# MAX-M8Q_GPS_FeatherWing.net
KiCad netlist of a schematic drawn in EAGLE
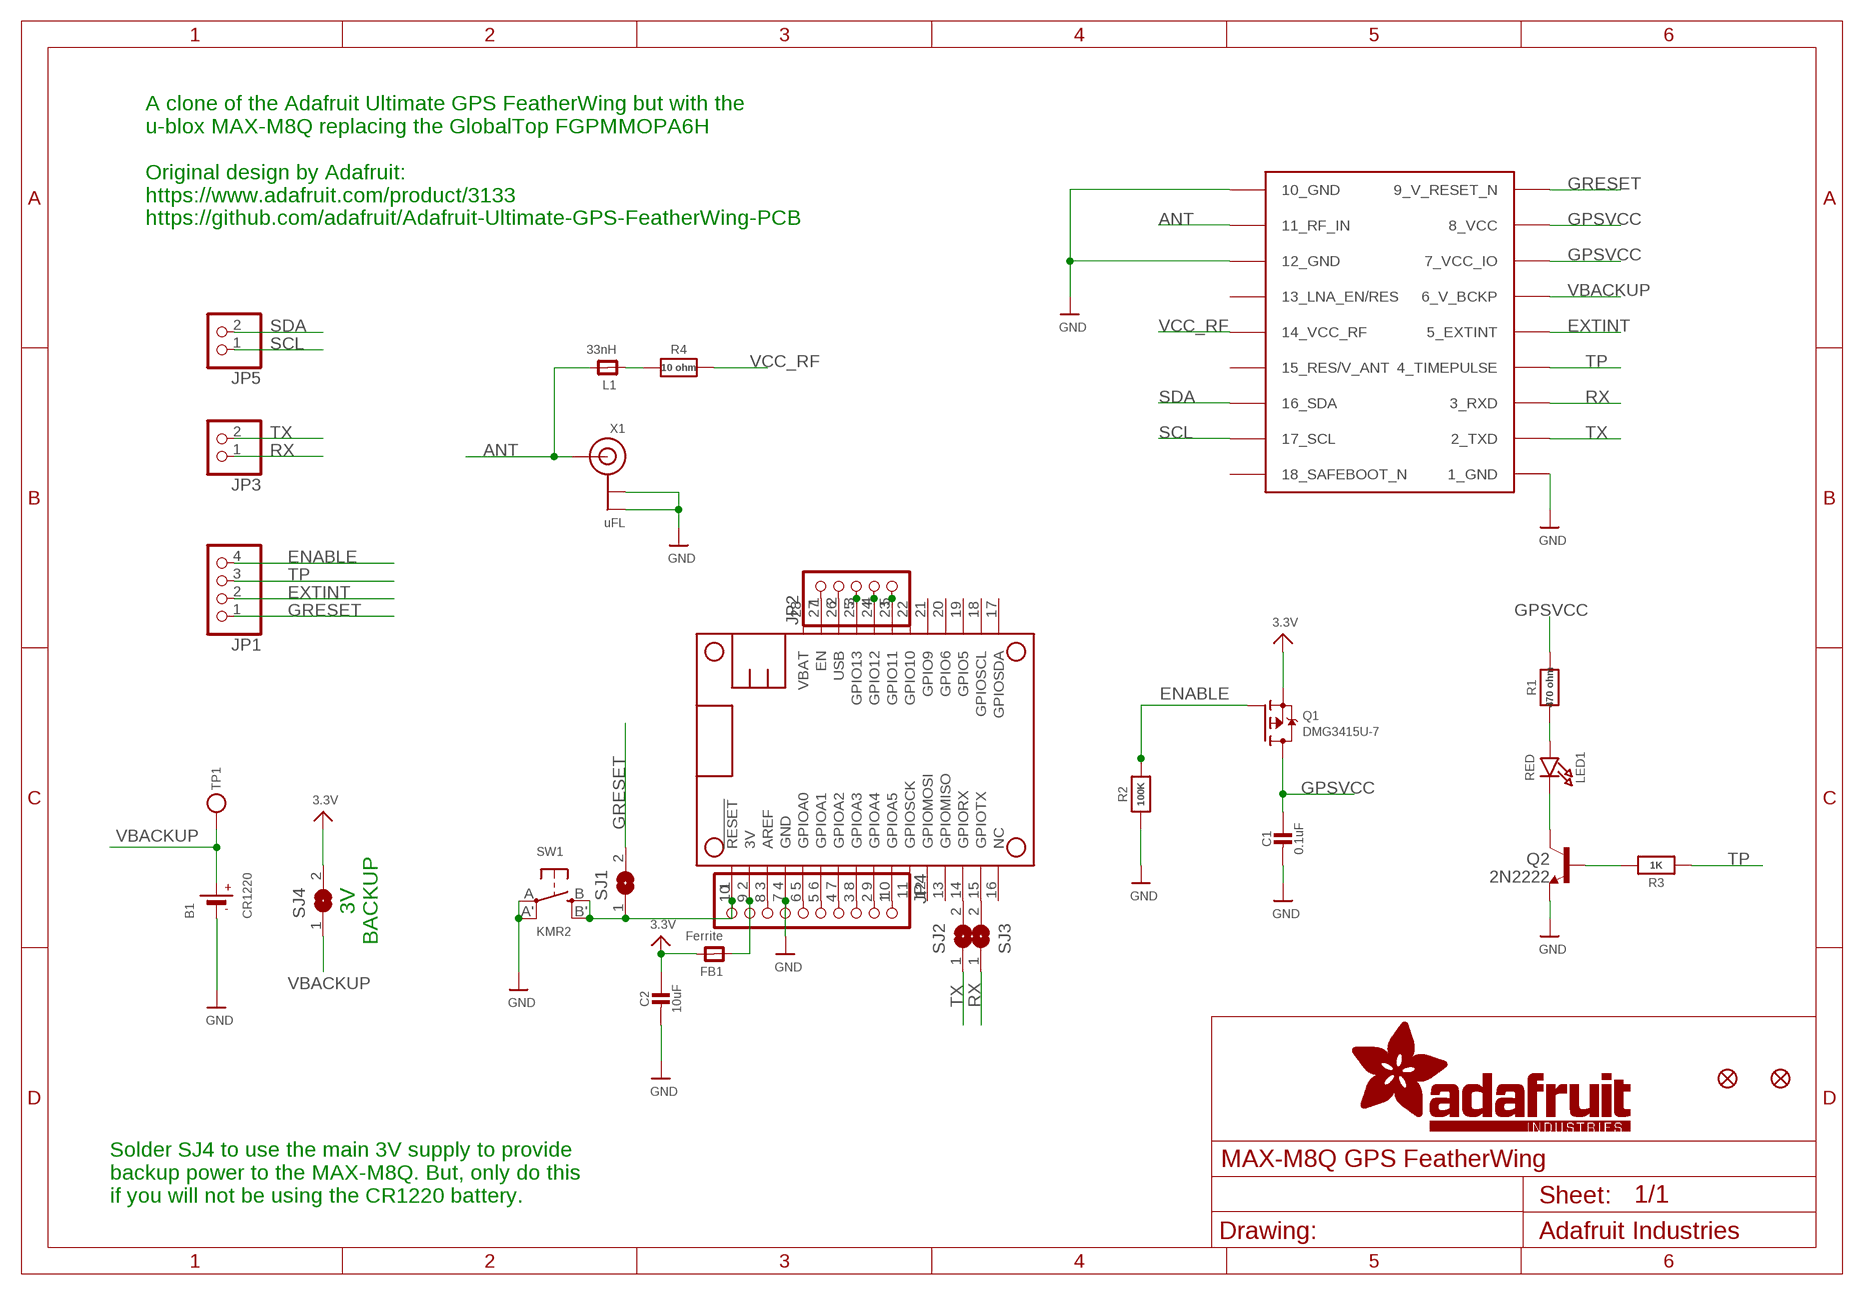
[diagram p0: schematic, sheet 1]

(export (version "E")
  (design (tool "Eeschema 10.0.6"))
  (components
    (comp (ref "B1")
      (value "CR1220")
      (footprint "eagle-import:CR1220-2")
      (libsource (lib "eagle-import") (part "BATTERYCR1220_2"))
    )
    (comp (ref "C1")
      (value "0.1uF")
      (footprint "eagle-import:0805-NO")
      (libsource (lib "eagle-import") (part "CAP_CERAMIC0805-NOOUTLINE"))
    )
    (comp (ref "C2")
      (value "10uF")
      (footprint "eagle-import:0805-NO")
      (libsource (lib "eagle-import") (part "CAP_CERAMIC0805-NOOUTLINE"))
    )
    (comp (ref "FB1")
      (value "Ferrite")
      (footprint "eagle-import:0805-NO")
      (libsource (lib "eagle-import") (part "FERRITE-0805NO"))
    )
    (comp (ref "FID1")
      (value "FIDUCIAL\"\"")
      (footprint "eagle-import:FIDUCIAL_1MM")
      (libsource (lib "eagle-import") (part "FIDUCIAL{dblquote}{dblquote}"))
    )
    (comp (ref "FID2")
      (value "FIDUCIAL\"\"")
      (footprint "eagle-import:FIDUCIAL_1MM")
      (libsource (lib "eagle-import") (part "FIDUCIAL{dblquote}{dblquote}"))
    )
    (comp (ref "JP1")
      (value "HEADER-1X4ROUND")
      (footprint "eagle-import:1X04_ROUND")
      (libsource (lib "eagle-import") (part "HEADER-1X4ROUND"))
    )
    (comp (ref "JP2")
      (value "HEADER-1X570MIL")
      (footprint "eagle-import:1X05_ROUND_70")
      (libsource (lib "eagle-import") (part "HEADER-1X570MIL"))
    )
    (comp (ref "JP3")
      (value "HEADER-1X2ROUND")
      (footprint "eagle-import:1X02_ROUND")
      (libsource (lib "eagle-import") (part "HEADER-1X2ROUND"))
    )
    (comp (ref "JP4")
      (value "HEADER-1X10ROUND")
      (footprint "eagle-import:1X10_ROUND")
      (libsource (lib "eagle-import") (part "HEADER-1X10ROUND"))
    )
    (comp (ref "JP5")
      (value "HEADER-1X2ROUND")
      (footprint "eagle-import:1X02_ROUND")
      (libsource (lib "eagle-import") (part "HEADER-1X2ROUND"))
    )
    (comp (ref "L1")
      (value "33nH")
      (footprint "eagle-import:0805-NO")
      (libsource (lib "eagle-import") (part "FERRITE-0805NO"))
    )
    (comp (ref "LED1")
      (value "RED")
      (footprint "eagle-import:CHIPLED_0805_NOOUTLINE")
      (libsource (lib "eagle-import") (part "LED0805_NOOUTLINE"))
    )
    (comp (ref "MS1")
      (value "FEATHERWING")
      (footprint "eagle-import:FEATHERWING")
      (libsource (lib "eagle-import") (part "FEATHERWING"))
    )
    (comp (ref "Q1")
      (value "DMG3415U-7")
      (footprint "eagle-import:SOT23-WIDE")
      (libsource (lib "eagle-import") (part "MOSFET-PWIDE"))
    )
    (comp (ref "Q2")
      (value "2N2222")
      (footprint "eagle-import:SOT23-BEC")
      (libsource (lib "eagle-import") (part "-NPN-SOT23-BECMMBT2222ALT1"))
    )
    (comp (ref "R1")
      (value "470 ohm")
      (footprint "eagle-import:0805-NO")
      (libsource (lib "eagle-import") (part "RESISTOR0805_NOOUTLINE"))
    )
    (comp (ref "R2")
      (value "100K")
      (footprint "eagle-import:0805-NO")
      (libsource (lib "eagle-import") (part "RESISTOR0805_NOOUTLINE"))
    )
    (comp (ref "R3")
      (value "1K")
      (footprint "eagle-import:0805-NO")
      (libsource (lib "eagle-import") (part "RESISTOR0805_NOOUTLINE"))
    )
    (comp (ref "R4")
      (value "10 ohm")
      (footprint "eagle-import:0805-NO")
      (libsource (lib "eagle-import") (part "RESISTOR0805_NOOUTLINE"))
    )
    (comp (ref "SJ1")
      (value "SOLDERJUMPER")
      (footprint "eagle-import:SOLDERJUMPER_ARROW_NOPASTE")
      (libsource (lib "eagle-import") (part "SOLDERJUMPER"))
    )
    (comp (ref "SJ2")
      (value "SOLDERJUMPERCLOSED")
      (footprint "eagle-import:SOLDERJUMPER_CLOSEDWIRE")
      (libsource (lib "eagle-import") (part "SOLDERJUMPERCLOSED"))
    )
    (comp (ref "SJ3")
      (value "SOLDERJUMPERCLOSED")
      (footprint "eagle-import:SOLDERJUMPER_CLOSEDWIRE")
      (libsource (lib "eagle-import") (part "SOLDERJUMPERCLOSED"))
    )
    (comp (ref "SJ4") (value "SJ") (footprint "eagle-import:SJ") (libsource (lib "eagle-import") (part "SJ")))
    (comp (ref "SW1")
      (value "KMR2")
      (footprint "eagle-import:BTN_KMR2_4.6X2.8")
      (libsource (lib "eagle-import") (part "SWITCH_TACT_SMT4.6X2.8"))
    )
    (comp (ref "TP1")
      (value "TESTPOINTROUND1.5MM")
      (footprint "eagle-import:TESTPOINT_ROUND_1.5MM")
      (libsource (lib "eagle-import") (part "TESTPOINTROUND1.5MM"))
    )
    (comp (ref "U1")
      (value "MAX-M8")
      (footprint "eagle-import:MAX-M8")
      (libsource (lib "eagle-import") (part "MAX-M8"))
    )
    (comp (ref "X1")
      (value "uFL")
      (footprint "eagle-import:U.FL")
      (libsource (lib "eagle-import") (part "ANTENNA_U.FL"))
    )
  )
  (nets
    (net (code "1") (name "/ANT") (class "Default")
      (node (ref "L1") (pin "2") (pinfunction "P$2_2") (pintype "passive"))
      (node (ref "U1") (pin "11_RF_IN") (pinfunction "11_RF_IN_11_RF_IN") (pintype "bidirectional"))
      (node (ref "X1") (pin "3") (pinfunction "SIGNAL_3") (pintype "passive"))
    )
    (net (code "2") (name "/ENABLE") (class "Default")
      (node (ref "JP1") (pin "4") (pinfunction "4_4") (pintype "passive"))
      (node (ref "Q1") (pin "1") (pinfunction "G_1") (pintype "passive"))
      (node (ref "R2") (pin "2") (pinfunction "2_2") (pintype "passive"))
    )
    (net (code "3") (name "/EXTINT") (class "Default")
      (node (ref "JP1") (pin "2") (pinfunction "2_2") (pintype "passive"))
      (node (ref "U1") (pin "5_EXTINT") (pinfunction "5_EXTINT_5_EXTINT") (pintype "bidirectional"))
    )
    (net (code "4") (name "/GPSVCC") (class "Default")
      (node (ref "C1") (pin "1") (pinfunction "1_1") (pintype "passive"))
      (node (ref "Q1") (pin "3") (pinfunction "D_3") (pintype "passive"))
      (node (ref "R1") (pin "2") (pinfunction "2_2") (pintype "passive"))
      (node (ref "U1") (pin "7_VCC_IO") (pinfunction "7_VCC_IO_7_VCC_IO") (pintype "power_in"))
      (node (ref "U1") (pin "8_VCC") (pinfunction "8_VCC_8_VCC") (pintype "power_in"))
    )
    (net (code "5") (name "/GRESET") (class "Default")
      (node (ref "JP1") (pin "1") (pinfunction "1_1") (pintype "passive"))
      (node (ref "SJ1") (pin "2") (pinfunction "2_2") (pintype "passive"))
      (node (ref "U1") (pin "9_RESET_N") (pinfunction "9_V_RESET_N_9_RESET_N") (pintype "power_in"))
    )
    (net (code "6") (name "/RX") (class "Default")
      (node (ref "JP3") (pin "1") (pinfunction "1_1") (pintype "passive"))
      (node (ref "SJ3") (pin "1") (pinfunction "1_1") (pintype "passive"))
      (node (ref "U1") (pin "3_RXD") (pinfunction "3_RXD_3_RXD") (pintype "bidirectional"))
    )
    (net (code "7") (name "/SCL") (class "Default")
      (node (ref "JP5") (pin "1") (pinfunction "1_1") (pintype "passive"))
      (node (ref "U1") (pin "17_SCL") (pinfunction "17_SCL_17_SCL") (pintype "bidirectional"))
    )
    (net (code "8") (name "/SDA") (class "Default")
      (node (ref "JP5") (pin "2") (pinfunction "2_2") (pintype "passive"))
      (node (ref "U1") (pin "16_SDA") (pinfunction "16_SDA_16_SDA") (pintype "bidirectional"))
    )
    (net (code "9") (name "/TP") (class "Default")
      (node (ref "JP1") (pin "3") (pinfunction "3_3") (pintype "passive"))
      (node (ref "R3") (pin "1") (pinfunction "1_1") (pintype "passive"))
      (node (ref "U1") (pin "4_TIMEPULSE") (pinfunction "4_TIMEPULSE_4_TIMEPULSE") (pintype "bidirectional"))
    )
    (net (code "10") (name "/TX") (class "Default")
      (node (ref "JP3") (pin "2") (pinfunction "2_2") (pintype "passive"))
      (node (ref "SJ2") (pin "1") (pinfunction "1_1") (pintype "passive"))
      (node (ref "U1") (pin "2_TXD") (pinfunction "2_TXD_2_TXD") (pintype "bidirectional"))
    )
    (net (code "11") (name "/VBACKUP") (class "Default")
      (node (ref "B1") (pin "+") (pinfunction "+_+") (pintype "passive"))
      (node (ref "SJ4") (pin "1") (pinfunction "1_1") (pintype "passive"))
      (node (ref "TP1") (pin "P$1") (pinfunction "P$1_P$1") (pintype "bidirectional"))
      (node (ref "U1") (pin "6_V_BCKP") (pinfunction "6_V_BCKP_6_V_BCKP") (pintype "bidirectional"))
    )
    (net (code "12") (name "/VBAT") (class "Default")
      (node (ref "MS1") (pin "28") (pinfunction "VBAT_28") (pintype "power_in"))
    )
    (net (code "13") (name "/VCC_RF") (class "Default")
      (node (ref "R4") (pin "2") (pinfunction "2_2") (pintype "passive"))
      (node (ref "U1") (pin "14_VCC_RF") (pinfunction "14_VCC_RF_14_VCC_RF") (pintype "bidirectional"))
    )
    (net (code "14") (name "3.3V") (class "Default")
      (node (ref "C2") (pin "1") (pinfunction "1_1") (pintype "passive"))
      (node (ref "FB1") (pin "2") (pinfunction "P$2_2") (pintype "passive"))
      (node (ref "Q1") (pin "2") (pinfunction "S_2") (pintype "passive"))
      (node (ref "SJ4") (pin "2") (pinfunction "2_2") (pintype "passive"))
    )
    (net (code "15") (name "GND") (class "Default")
      (node (ref "B1") (pin "-") (pinfunction "-_-") (pintype "passive"))
      (node (ref "C1") (pin "2") (pinfunction "2_2") (pintype "passive"))
      (node (ref "C2") (pin "2") (pinfunction "2_2") (pintype "passive"))
      (node (ref "JP4") (pin "7") (pinfunction "7_7") (pintype "passive"))
      (node (ref "MS1") (pin "4") (pinfunction "GND_4") (pintype "power_in"))
      (node (ref "Q2") (pin "E") (pinfunction "E_E") (pintype "passive"))
      (node (ref "R2") (pin "1") (pinfunction "1_1") (pintype "passive"))
      (node (ref "SW1") (pin "A") (pinfunction "P_A") (pintype "passive"))
      (node (ref "SW1") (pin "A'") (pinfunction "P1_A'") (pintype "passive"))
      (node (ref "U1") (pin "10_GND") (pinfunction "10_GND_10_GND") (pintype "power_in"))
      (node (ref "U1") (pin "12_GND") (pinfunction "12_GND_12_GND") (pintype "power_in"))
      (node (ref "U1") (pin "1_GND") (pinfunction "1_GND_1_GND") (pintype "power_in"))
      (node (ref "X1") (pin "1") (pinfunction "GND_1") (pintype "passive"))
      (node (ref "X1") (pin "2") (pinfunction "GND_2") (pintype "passive"))
    )
    (net (code "16") (name "Net-(FB1-P$1)") (class "Default")
      (node (ref "FB1") (pin "1") (pinfunction "P$1_1") (pintype "passive"))
      (node (ref "JP4") (pin "9") (pinfunction "9_9") (pintype "passive"))
      (node (ref "MS1") (pin "2") (pinfunction "3V_2") (pintype "power_in"))
    )
    (net (code "17") (name "Net-(L1-P$1)") (class "Default")
      (node (ref "L1") (pin "1") (pinfunction "P$1_1") (pintype "passive"))
      (node (ref "R4") (pin "1") (pinfunction "1_1") (pintype "passive"))
    )
    (net (code "18") (name "Net-(LED1-PadA)") (class "Default")
      (node (ref "LED1") (pin "A") (pinfunction "A_A") (pintype "passive"))
      (node (ref "R1") (pin "1") (pinfunction "1_1") (pintype "passive"))
    )
    (net (code "19") (name "Net-(LED1-PadC)") (class "Default")
      (node (ref "LED1") (pin "C") (pinfunction "C_C") (pintype "passive"))
      (node (ref "Q2") (pin "C") (pinfunction "C_C") (pintype "passive"))
    )
    (net (code "20") (name "Net-(MS1-AREF)") (class "Default")
      (node (ref "JP4") (pin "8") (pinfunction "8_8") (pintype "passive"))
      (node (ref "MS1") (pin "3") (pinfunction "AREF_3") (pintype "passive"))
    )
    (net (code "21") (name "Net-(MS1-EN)") (class "Default")
      (node (ref "JP2") (pin "1") (pinfunction "1_1") (pintype "passive"))
      (node (ref "MS1") (pin "27") (pinfunction "EN_27") (pintype "passive"))
    )
    (net (code "22") (name "Net-(MS1-GPIO11)") (class "Default")
      (node (ref "JP2") (pin "5") (pinfunction "5_5") (pintype "passive"))
      (node (ref "MS1") (pin "23") (pinfunction "GPIO11_23") (pintype "bidirectional"))
    )
    (net (code "23") (name "Net-(MS1-GPIO12)") (class "Default")
      (node (ref "JP2") (pin "4") (pinfunction "4_4") (pintype "passive"))
      (node (ref "MS1") (pin "24") (pinfunction "GPIO12_24") (pintype "bidirectional"))
    )
    (net (code "24") (name "Net-(MS1-GPIO13)") (class "Default")
      (node (ref "JP2") (pin "3") (pinfunction "3_3") (pintype "passive"))
      (node (ref "MS1") (pin "25") (pinfunction "GPIO13_25") (pintype "bidirectional"))
    )
    (net (code "25") (name "Net-(MS1-GPIOA0)") (class "Default")
      (node (ref "JP4") (pin "6") (pinfunction "6_6") (pintype "passive"))
      (node (ref "MS1") (pin "5") (pinfunction "GPIOA0_5") (pintype "bidirectional"))
    )
    (net (code "26") (name "Net-(MS1-GPIOA1)") (class "Default")
      (node (ref "JP4") (pin "5") (pinfunction "5_5") (pintype "passive"))
      (node (ref "MS1") (pin "6") (pinfunction "GPIOA1_6") (pintype "bidirectional"))
    )
    (net (code "27") (name "Net-(MS1-GPIOA2)") (class "Default")
      (node (ref "JP4") (pin "4") (pinfunction "4_4") (pintype "passive"))
      (node (ref "MS1") (pin "7") (pinfunction "GPIOA2_7") (pintype "bidirectional"))
    )
    (net (code "28") (name "Net-(MS1-GPIOA3)") (class "Default")
      (node (ref "JP4") (pin "3") (pinfunction "3_3") (pintype "passive"))
      (node (ref "MS1") (pin "8") (pinfunction "GPIOA3_8") (pintype "bidirectional"))
    )
    (net (code "29") (name "Net-(MS1-GPIOA4)") (class "Default")
      (node (ref "JP4") (pin "2") (pinfunction "2_2") (pintype "passive"))
      (node (ref "MS1") (pin "9") (pinfunction "GPIOA4_9") (pintype "bidirectional"))
    )
    (net (code "30") (name "Net-(MS1-GPIOA5)") (class "Default")
      (node (ref "JP4") (pin "1") (pinfunction "1_1") (pintype "passive"))
      (node (ref "MS1") (pin "10") (pinfunction "GPIOA5_10") (pintype "bidirectional"))
    )
    (net (code "31") (name "Net-(MS1-GPIORX)") (class "Default")
      (node (ref "MS1") (pin "14") (pinfunction "GPIORX_14") (pintype "bidirectional"))
      (node (ref "SJ2") (pin "2") (pinfunction "2_2") (pintype "passive"))
    )
    (net (code "32") (name "Net-(MS1-GPIOTX)") (class "Default")
      (node (ref "MS1") (pin "15") (pinfunction "GPIOTX_15") (pintype "bidirectional"))
      (node (ref "SJ3") (pin "2") (pinfunction "2_2") (pintype "passive"))
    )
    (net (code "33") (name "Net-(MS1-USB)") (class "Default")
      (node (ref "JP2") (pin "2") (pinfunction "2_2") (pintype "passive"))
      (node (ref "MS1") (pin "26") (pinfunction "USB_26") (pintype "power_in"))
    )
    (net (code "34") (name "Net-(MS1-~{RESET})") (class "Default")
      (node (ref "JP4") (pin "10") (pinfunction "10_10") (pintype "passive"))
      (node (ref "MS1") (pin "1") (pinfunction "~{RESET}_1") (pintype "input"))
      (node (ref "SJ1") (pin "1") (pinfunction "1_1") (pintype "passive"))
      (node (ref "SW1") (pin "B") (pinfunction "S_B") (pintype "passive"))
      (node (ref "SW1") (pin "B'") (pinfunction "S1_B'") (pintype "passive"))
    )
    (net (code "35") (name "Net-(Q2-PadB)") (class "Default")
      (node (ref "Q2") (pin "B") (pinfunction "B_B") (pintype "passive"))
      (node (ref "R3") (pin "2") (pinfunction "2_2") (pintype "passive"))
    )
    (net (code "36") (name "unconnected-(MS1-GPIO5-Pad19)") (class "Default")
      (node (ref "MS1") (pin "19") (pinfunction "GPIO5_19") (pintype "bidirectional"))
    )
    (net (code "37") (name "unconnected-(MS1-GPIO6-Pad20)") (class "Default")
      (node (ref "MS1") (pin "20") (pinfunction "GPIO6_20") (pintype "bidirectional"))
    )
    (net (code "38") (name "unconnected-(MS1-GPIO9-Pad21)") (class "Default")
      (node (ref "MS1") (pin "21") (pinfunction "GPIO9_21") (pintype "bidirectional"))
    )
    (net (code "39") (name "unconnected-(MS1-GPIO10-Pad22)") (class "Default")
      (node (ref "MS1") (pin "22") (pinfunction "GPIO10_22") (pintype "bidirectional"))
    )
    (net (code "40") (name "unconnected-(MS1-GPIOMISO-Pad13)") (class "Default")
      (node (ref "MS1") (pin "13") (pinfunction "GPIOMISO_13") (pintype "bidirectional"))
    )
    (net (code "41") (name "unconnected-(MS1-GPIOMOSI-Pad12)") (class "Default")
      (node (ref "MS1") (pin "12") (pinfunction "GPIOMOSI_12") (pintype "bidirectional"))
    )
    (net (code "42") (name "unconnected-(MS1-GPIOSCK-Pad11)") (class "Default")
      (node (ref "MS1") (pin "11") (pinfunction "GPIOSCK_11") (pintype "bidirectional"))
    )
    (net (code "43") (name "unconnected-(MS1-GPIOSCL-Pad18)") (class "Default")
      (node (ref "MS1") (pin "18") (pinfunction "GPIOSCL_18") (pintype "bidirectional"))
    )
    (net (code "44") (name "unconnected-(MS1-GPIOSDA-Pad17)") (class "Default")
      (node (ref "MS1") (pin "17") (pinfunction "GPIOSDA_17") (pintype "bidirectional"))
    )
    (net (code "45") (name "unconnected-(MS1-NC-Pad16)") (class "Default")
      (node (ref "MS1") (pin "16") (pinfunction "NC_16") (pintype "passive"))
    )
    (net (code "46") (name "unconnected-(U1-13_LNA_EN{slash}RES-Pad13_LNA_EN)") (class "Default")
      (node (ref "U1") (pin "13_LNA_EN") (pinfunction "13_LNA_EN/RES_13_LNA_EN") (pintype "bidirectional"))
    )
    (net (code "47") (name "unconnected-(U1-15_RES{slash}V_ANT-Pad15_V_ANT{slash}RESERVED)") (class "Default")
      (node (ref "U1") (pin "15_V_ANT/RESERVED") (pinfunction "15_RES/V_ANT_15_V_ANT/RESERVED") (pintype "bidirectional"))
    )
    (net (code "48") (name "unconnected-(U1-Pad18_SAFEBOOT_N)") (class "Default")
      (node (ref "U1") (pin "18_SAFEBOOT_N") (pinfunction "18_SAFEBOOT_N_18_SAFEBOOT_N") (pintype "bidirectional"))
    )
  )
)
